# mpu_power.net
KiCad netlist of a schematic drawn in Altium Designer
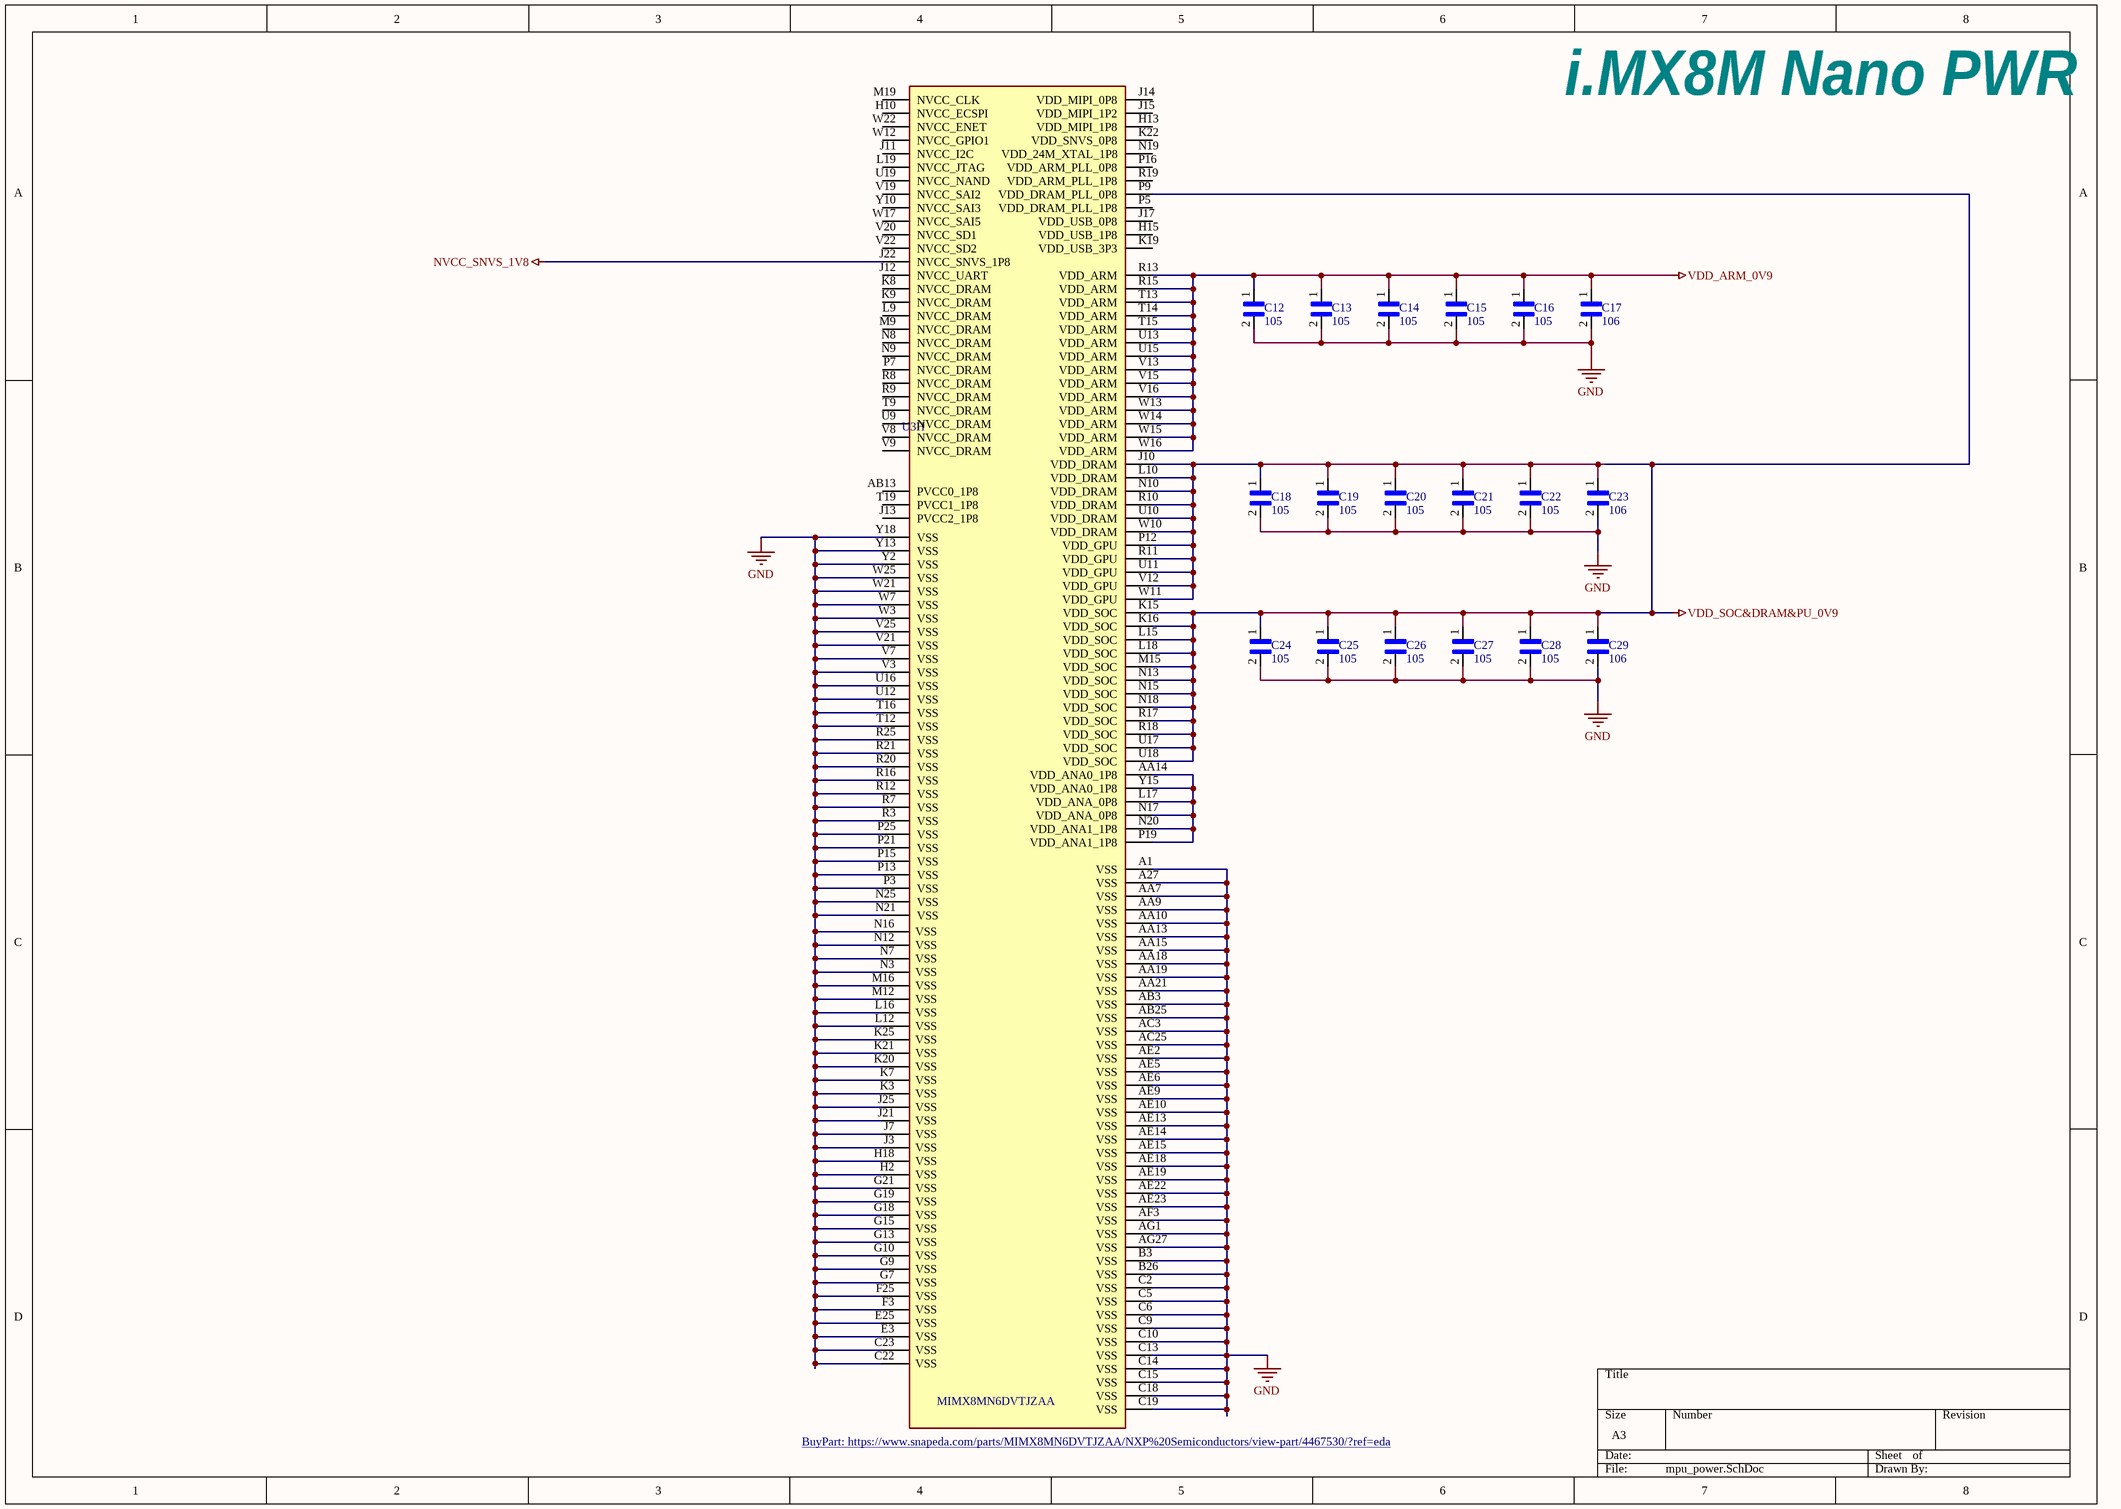
[diagram p0: mpu_power.SchDoc]

(export (version "E")
  (design (tool "Eeschema 10.0.6"))
  (components
    (comp (ref "C12")
      (value "105")
      (footprint "RC0402")
      (description "Multilayer Ceramic Capacitor, 1 uF, 100 V, ï¿½ 10%, X7R, 0402 [1005 Metric]")
      (fields
        (field (name "MANUFACTURER") "Yageo")
        (field (name "MANUFACTURER PART NUMBER") "CC0402KRX5R5BB105")
      )
      (libsource (lib "imx8mnano") (part "CC0402KRX5R5BB105"))
    )
    (comp (ref "C13")
      (value "105")
      (footprint "RC0402")
      (description "Multilayer Ceramic Capacitor, 1 uF, 100 V, ï¿½ 10%, X7R, 0402 [1005 Metric]")
      (fields
        (field (name "MANUFACTURER") "Yageo")
        (field (name "MANUFACTURER PART NUMBER") "CC0402KRX5R5BB105")
      )
      (libsource (lib "imx8mnano") (part "CC0402KRX5R5BB105"))
    )
    (comp (ref "C14")
      (value "105")
      (footprint "RC0402")
      (description "Multilayer Ceramic Capacitor, 1 uF, 100 V, ï¿½ 10%, X7R, 0402 [1005 Metric]")
      (fields
        (field (name "MANUFACTURER") "Yageo")
        (field (name "MANUFACTURER PART NUMBER") "CC0402KRX5R5BB105")
      )
      (libsource (lib "imx8mnano") (part "CC0402KRX5R5BB105"))
    )
    (comp (ref "C15")
      (value "105")
      (footprint "RC0402")
      (description "Multilayer Ceramic Capacitor, 1 uF, 100 V, ï¿½ 10%, X7R, 0402 [1005 Metric]")
      (fields
        (field (name "MANUFACTURER") "Yageo")
        (field (name "MANUFACTURER PART NUMBER") "CC0402KRX5R5BB105")
      )
      (libsource (lib "imx8mnano") (part "CC0402KRX5R5BB105"))
    )
    (comp (ref "C16")
      (value "105")
      (footprint "RC0402")
      (description "Multilayer Ceramic Capacitor, 1 uF, 100 V, ï¿½ 10%, X7R, 0402 [1005 Metric]")
      (fields
        (field (name "MANUFACTURER") "Yageo")
        (field (name "MANUFACTURER PART NUMBER") "CC0402KRX5R5BB105")
      )
      (libsource (lib "imx8mnano") (part "CC0402KRX5R5BB105"))
    )
    (comp (ref "C17")
      (value "106")
      (footprint "CL05A106MQ5NUNC")
      (description "Multilayer Ceramic Capacitor, 10 uF, 6.3 V, ï¿½ 20%, X5R, 0402 [1005 Metric]")
      (fields
        (field (name "MANUFACTURER") "Samsung")
        (field (name "MANUFACTURER PART NUMBER") "CL05A106MQ5NUNC")
      )
      (libsource (lib "imx8mnano") (part "CL05A106MQ5NUNC"))
    )
    (comp (ref "C18")
      (value "105")
      (footprint "RC0402")
      (description "Multilayer Ceramic Capacitor, 1 uF, 100 V, ï¿½ 10%, X7R, 0402 [1005 Metric]")
      (fields
        (field (name "MANUFACTURER") "Yageo")
        (field (name "MANUFACTURER PART NUMBER") "CC0402KRX5R5BB105")
      )
      (libsource (lib "imx8mnano") (part "CC0402KRX5R5BB105"))
    )
    (comp (ref "C19")
      (value "105")
      (footprint "RC0402")
      (description "Multilayer Ceramic Capacitor, 1 uF, 100 V, ï¿½ 10%, X7R, 0402 [1005 Metric]")
      (fields
        (field (name "MANUFACTURER") "Yageo")
        (field (name "MANUFACTURER PART NUMBER") "CC0402KRX5R5BB105")
      )
      (libsource (lib "imx8mnano") (part "CC0402KRX5R5BB105"))
    )
    (comp (ref "C20")
      (value "105")
      (footprint "RC0402")
      (description "Multilayer Ceramic Capacitor, 1 uF, 100 V, ï¿½ 10%, X7R, 0402 [1005 Metric]")
      (fields
        (field (name "MANUFACTURER") "Yageo")
        (field (name "MANUFACTURER PART NUMBER") "CC0402KRX5R5BB105")
      )
      (libsource (lib "imx8mnano") (part "CC0402KRX5R5BB105"))
    )
    (comp (ref "C21")
      (value "105")
      (footprint "RC0402")
      (description "Multilayer Ceramic Capacitor, 1 uF, 100 V, ï¿½ 10%, X7R, 0402 [1005 Metric]")
      (fields
        (field (name "MANUFACTURER") "Yageo")
        (field (name "MANUFACTURER PART NUMBER") "CC0402KRX5R5BB105")
      )
      (libsource (lib "imx8mnano") (part "CC0402KRX5R5BB105"))
    )
    (comp (ref "C22")
      (value "105")
      (footprint "RC0402")
      (description "Multilayer Ceramic Capacitor, 1 uF, 100 V, ï¿½ 10%, X7R, 0402 [1005 Metric]")
      (fields
        (field (name "MANUFACTURER") "Yageo")
        (field (name "MANUFACTURER PART NUMBER") "CC0402KRX5R5BB105")
      )
      (libsource (lib "imx8mnano") (part "CC0402KRX5R5BB105"))
    )
    (comp (ref "C23")
      (value "106")
      (footprint "CL05A106MQ5NUNC")
      (description "Multilayer Ceramic Capacitor, 10 uF, 6.3 V, ï¿½ 20%, X5R, 0402 [1005 Metric]")
      (fields
        (field (name "MANUFACTURER") "Samsung")
        (field (name "MANUFACTURER PART NUMBER") "CL05A106MQ5NUNC")
      )
      (libsource (lib "imx8mnano") (part "CL05A106MQ5NUNC"))
    )
    (comp (ref "C24")
      (value "105")
      (footprint "RC0402")
      (description "Multilayer Ceramic Capacitor, 1 uF, 100 V, ï¿½ 10%, X7R, 0402 [1005 Metric]")
      (fields
        (field (name "MANUFACTURER") "Yageo")
        (field (name "MANUFACTURER PART NUMBER") "CC0402KRX5R5BB105")
      )
      (libsource (lib "imx8mnano") (part "CC0402KRX5R5BB105"))
    )
    (comp (ref "C25")
      (value "105")
      (footprint "RC0402")
      (description "Multilayer Ceramic Capacitor, 1 uF, 100 V, ï¿½ 10%, X7R, 0402 [1005 Metric]")
      (fields
        (field (name "MANUFACTURER") "Yageo")
        (field (name "MANUFACTURER PART NUMBER") "CC0402KRX5R5BB105")
      )
      (libsource (lib "imx8mnano") (part "CC0402KRX5R5BB105"))
    )
    (comp (ref "C26")
      (value "105")
      (footprint "RC0402")
      (description "Multilayer Ceramic Capacitor, 1 uF, 100 V, ï¿½ 10%, X7R, 0402 [1005 Metric]")
      (fields
        (field (name "MANUFACTURER") "Yageo")
        (field (name "MANUFACTURER PART NUMBER") "CC0402KRX5R5BB105")
      )
      (libsource (lib "imx8mnano") (part "CC0402KRX5R5BB105"))
    )
    (comp (ref "C27")
      (value "105")
      (footprint "RC0402")
      (description "Multilayer Ceramic Capacitor, 1 uF, 100 V, ï¿½ 10%, X7R, 0402 [1005 Metric]")
      (fields
        (field (name "MANUFACTURER") "Yageo")
        (field (name "MANUFACTURER PART NUMBER") "CC0402KRX5R5BB105")
      )
      (libsource (lib "imx8mnano") (part "CC0402KRX5R5BB105"))
    )
    (comp (ref "C28")
      (value "105")
      (footprint "RC0402")
      (description "Multilayer Ceramic Capacitor, 1 uF, 100 V, ï¿½ 10%, X7R, 0402 [1005 Metric]")
      (fields
        (field (name "MANUFACTURER") "Yageo")
        (field (name "MANUFACTURER PART NUMBER") "CC0402KRX5R5BB105")
      )
      (libsource (lib "imx8mnano") (part "CC0402KRX5R5BB105"))
    )
    (comp (ref "C29")
      (value "106")
      (footprint "CL05A106MQ5NUNC")
      (description "Multilayer Ceramic Capacitor, 10 uF, 6.3 V, ï¿½ 20%, X5R, 0402 [1005 Metric]")
      (fields
        (field (name "MANUFACTURER") "Samsung")
        (field (name "MANUFACTURER PART NUMBER") "CL05A106MQ5NUNC")
      )
      (libsource (lib "imx8mnano") (part "CL05A106MQ5NUNC"))
    )
    (comp (ref "U3")
      (value "MIMX8MN6DVTJZAA")
      (footprint "BGA486N50P27X27_1400X1400X125N")
      (description "ARMÂ® CortexÂ®-A53 Microprocessor IC i.MX8MN 4 Core, 32-Bit 1.5GHz 486-LFBGA (14x14)")
      (fields
        (field (name "MF") "NXP USA Inc.")
        (field (name "BUYPART") "https://www.snapeda.com/parts/MIMX8MN6DVTJZAA/NXP%20Semiconductors/view-part/4467530/?ref=eda")
      )
      (libsource (lib "imx8mnano") (part "MIMX8MN6DVTJZAA"))
    )
  )
  (nets
    (net (code "1") (name "GND") (class "Default")
      (node (ref "C12") (pin "2") (pinfunction "2_2") (pintype "passive"))
      (node (ref "C13") (pin "2") (pinfunction "2_2") (pintype "passive"))
      (node (ref "C14") (pin "2") (pinfunction "2_2") (pintype "passive"))
      (node (ref "C15") (pin "2") (pinfunction "2_2") (pintype "passive"))
      (node (ref "C16") (pin "2") (pinfunction "2_2") (pintype "passive"))
      (node (ref "C17") (pin "2") (pinfunction "2_2") (pintype "passive"))
      (node (ref "C18") (pin "2") (pinfunction "2_2") (pintype "passive"))
      (node (ref "C19") (pin "2") (pinfunction "2_2") (pintype "passive"))
      (node (ref "C20") (pin "2") (pinfunction "2_2") (pintype "passive"))
      (node (ref "C21") (pin "2") (pinfunction "2_2") (pintype "passive"))
      (node (ref "C22") (pin "2") (pinfunction "2_2") (pintype "passive"))
      (node (ref "C23") (pin "2") (pinfunction "2_2") (pintype "passive"))
      (node (ref "C24") (pin "2") (pinfunction "2_2") (pintype "passive"))
      (node (ref "C25") (pin "2") (pinfunction "2_2") (pintype "passive"))
      (node (ref "C26") (pin "2") (pinfunction "2_2") (pintype "passive"))
      (node (ref "C27") (pin "2") (pinfunction "2_2") (pintype "passive"))
      (node (ref "C28") (pin "2") (pinfunction "2_2") (pintype "passive"))
      (node (ref "C29") (pin "2") (pinfunction "2_2") (pintype "passive"))
      (node (ref "U3") (pin "A1") (pinfunction "VSS_A1") (pintype "power_in"))
      (node (ref "U3") (pin "A27") (pinfunction "VSS_A27") (pintype "power_in"))
      (node (ref "U3") (pin "AA10") (pinfunction "VSS_AA10") (pintype "power_in"))
      (node (ref "U3") (pin "AA13") (pinfunction "VSS_AA13") (pintype "power_in"))
      (node (ref "U3") (pin "AA18") (pinfunction "VSS_AA18") (pintype "power_in"))
      (node (ref "U3") (pin "AA19") (pinfunction "VSS_AA19") (pintype "power_in"))
      (node (ref "U3") (pin "AA21") (pinfunction "VSS_AA21") (pintype "power_in"))
      (node (ref "U3") (pin "AA7") (pinfunction "VSS_AA7") (pintype "power_in"))
      (node (ref "U3") (pin "AA9") (pinfunction "VSS_AA9") (pintype "power_in"))
      (node (ref "U3") (pin "AB25") (pinfunction "VSS_AB25") (pintype "power_in"))
      (node (ref "U3") (pin "AB3") (pinfunction "VSS_AB3") (pintype "power_in"))
      (node (ref "U3") (pin "AC25") (pinfunction "VSS_AC25") (pintype "power_in"))
      (node (ref "U3") (pin "AC3") (pinfunction "VSS_AC3") (pintype "power_in"))
      (node (ref "U3") (pin "AE10") (pinfunction "VSS_AE10") (pintype "power_in"))
      (node (ref "U3") (pin "AE13") (pinfunction "VSS_AE13") (pintype "power_in"))
      (node (ref "U3") (pin "AE14") (pinfunction "VSS_AE14") (pintype "power_in"))
      (node (ref "U3") (pin "AE15") (pinfunction "VSS_AE15") (pintype "power_in"))
      (node (ref "U3") (pin "AE18") (pinfunction "VSS_AE18") (pintype "power_in"))
      (node (ref "U3") (pin "AE19") (pinfunction "VSS_AE19") (pintype "power_in"))
      (node (ref "U3") (pin "AE2") (pinfunction "VSS_AE2") (pintype "power_in"))
      (node (ref "U3") (pin "AE22") (pinfunction "VSS_AE22") (pintype "power_in"))
      (node (ref "U3") (pin "AE23") (pinfunction "VSS_AE23") (pintype "power_in"))
      (node (ref "U3") (pin "AE5") (pinfunction "VSS_AE5") (pintype "power_in"))
      (node (ref "U3") (pin "AE6") (pinfunction "VSS_AE6") (pintype "power_in"))
      (node (ref "U3") (pin "AE9") (pinfunction "VSS_AE9") (pintype "power_in"))
      (node (ref "U3") (pin "AF3") (pinfunction "VSS_AF3") (pintype "power_in"))
      (node (ref "U3") (pin "AG1") (pinfunction "VSS_AG1") (pintype "power_in"))
      (node (ref "U3") (pin "AG27") (pinfunction "VSS_AG27") (pintype "power_in"))
      (node (ref "U3") (pin "B26") (pinfunction "VSS_B26") (pintype "power_in"))
      (node (ref "U3") (pin "B3") (pinfunction "VSS_B3") (pintype "power_in"))
      (node (ref "U3") (pin "C10") (pinfunction "VSS_C10") (pintype "power_in"))
      (node (ref "U3") (pin "C13") (pinfunction "VSS_C13") (pintype "power_in"))
      (node (ref "U3") (pin "C14") (pinfunction "VSS_C14") (pintype "power_in"))
      (node (ref "U3") (pin "C15") (pinfunction "VSS_C15") (pintype "power_in"))
      (node (ref "U3") (pin "C18") (pinfunction "VSS_C18") (pintype "power_in"))
      (node (ref "U3") (pin "C19") (pinfunction "VSS_C19") (pintype "power_in"))
      (node (ref "U3") (pin "C2") (pinfunction "VSS_C2") (pintype "power_in"))
      (node (ref "U3") (pin "C22") (pinfunction "VSS_C22") (pintype "power_in"))
      (node (ref "U3") (pin "C23") (pinfunction "VSS_C23") (pintype "power_in"))
      (node (ref "U3") (pin "C5") (pinfunction "VSS_C5") (pintype "power_in"))
      (node (ref "U3") (pin "C6") (pinfunction "VSS_C6") (pintype "power_in"))
      (node (ref "U3") (pin "C9") (pinfunction "VSS_C9") (pintype "power_in"))
      (node (ref "U3") (pin "E25") (pinfunction "VSS_E25") (pintype "power_in"))
      (node (ref "U3") (pin "E3") (pinfunction "VSS_E3") (pintype "power_in"))
      (node (ref "U3") (pin "F25") (pinfunction "VSS_F25") (pintype "power_in"))
      (node (ref "U3") (pin "F3") (pinfunction "VSS_F3") (pintype "power_in"))
      (node (ref "U3") (pin "G10") (pinfunction "VSS_G10") (pintype "power_in"))
      (node (ref "U3") (pin "G13") (pinfunction "VSS_G13") (pintype "power_in"))
      (node (ref "U3") (pin "G15") (pinfunction "VSS_G15") (pintype "power_in"))
      (node (ref "U3") (pin "G18") (pinfunction "VSS_G18") (pintype "power_in"))
      (node (ref "U3") (pin "G19") (pinfunction "VSS_G19") (pintype "power_in"))
      (node (ref "U3") (pin "G21") (pinfunction "VSS_G21") (pintype "power_in"))
      (node (ref "U3") (pin "G7") (pinfunction "VSS_G7") (pintype "power_in"))
      (node (ref "U3") (pin "G9") (pinfunction "VSS_G9") (pintype "power_in"))
      (node (ref "U3") (pin "H18") (pinfunction "VSS_H18") (pintype "power_in"))
      (node (ref "U3") (pin "H2") (pinfunction "VSS_H2") (pintype "power_in"))
      (node (ref "U3") (pin "J21") (pinfunction "VSS_J21") (pintype "power_in"))
      (node (ref "U3") (pin "J25") (pinfunction "VSS_J25") (pintype "power_in"))
      (node (ref "U3") (pin "J3") (pinfunction "VSS_J3") (pintype "power_in"))
      (node (ref "U3") (pin "J7") (pinfunction "VSS_J7") (pintype "power_in"))
      (node (ref "U3") (pin "K20") (pinfunction "VSS_K20") (pintype "power_in"))
      (node (ref "U3") (pin "K21") (pinfunction "VSS_K21") (pintype "power_in"))
      (node (ref "U3") (pin "K25") (pinfunction "VSS_K25") (pintype "power_in"))
      (node (ref "U3") (pin "K3") (pinfunction "VSS_K3") (pintype "power_in"))
      (node (ref "U3") (pin "K7") (pinfunction "VSS_K7") (pintype "power_in"))
      (node (ref "U3") (pin "L12") (pinfunction "VSS_L12") (pintype "power_in"))
      (node (ref "U3") (pin "L16") (pinfunction "VSS_L16") (pintype "power_in"))
      (node (ref "U3") (pin "M12") (pinfunction "VSS_M12") (pintype "power_in"))
      (node (ref "U3") (pin "M16") (pinfunction "VSS_M16") (pintype "power_in"))
      (node (ref "U3") (pin "N12") (pinfunction "VSS_N12") (pintype "power_in"))
      (node (ref "U3") (pin "N16") (pinfunction "VSS_N16") (pintype "power_in"))
      (node (ref "U3") (pin "N21") (pinfunction "VSS_N21") (pintype "power_in"))
      (node (ref "U3") (pin "N25") (pinfunction "VSS_N25") (pintype "power_in"))
      (node (ref "U3") (pin "N3") (pinfunction "VSS_N3") (pintype "power_in"))
      (node (ref "U3") (pin "N7") (pinfunction "VSS_N7") (pintype "power_in"))
      (node (ref "U3") (pin "P13") (pinfunction "VSS_P13") (pintype "power_in"))
      (node (ref "U3") (pin "P15") (pinfunction "VSS_P15") (pintype "power_in"))
      (node (ref "U3") (pin "P21") (pinfunction "VSS_P21") (pintype "power_in"))
      (node (ref "U3") (pin "P25") (pinfunction "VSS_P25") (pintype "power_in"))
      (node (ref "U3") (pin "P3") (pinfunction "VSS_P3") (pintype "power_in"))
      (node (ref "U3") (pin "R12") (pinfunction "VSS_R12") (pintype "power_in"))
      (node (ref "U3") (pin "R16") (pinfunction "VSS_R16") (pintype "power_in"))
      (node (ref "U3") (pin "R20") (pinfunction "VSS_R20") (pintype "power_in"))
      (node (ref "U3") (pin "R21") (pinfunction "VSS_R21") (pintype "power_in"))
      (node (ref "U3") (pin "R25") (pinfunction "VSS_R25") (pintype "power_in"))
      (node (ref "U3") (pin "R3") (pinfunction "VSS_R3") (pintype "power_in"))
      (node (ref "U3") (pin "R7") (pinfunction "VSS_R7") (pintype "power_in"))
      (node (ref "U3") (pin "T12") (pinfunction "VSS_T12") (pintype "power_in"))
      (node (ref "U3") (pin "T16") (pinfunction "VSS_T16") (pintype "power_in"))
      (node (ref "U3") (pin "U12") (pinfunction "VSS_U12") (pintype "power_in"))
      (node (ref "U3") (pin "U16") (pinfunction "VSS_U16") (pintype "power_in"))
      (node (ref "U3") (pin "V21") (pinfunction "VSS_V21") (pintype "power_in"))
      (node (ref "U3") (pin "V25") (pinfunction "VSS_V25") (pintype "power_in"))
      (node (ref "U3") (pin "V3") (pinfunction "VSS_V3") (pintype "power_in"))
      (node (ref "U3") (pin "V7") (pinfunction "VSS_V7") (pintype "power_in"))
      (node (ref "U3") (pin "W21") (pinfunction "VSS_W21") (pintype "power_in"))
      (node (ref "U3") (pin "W25") (pinfunction "VSS_W25") (pintype "power_in"))
      (node (ref "U3") (pin "W3") (pinfunction "VSS_W3") (pintype "power_in"))
      (node (ref "U3") (pin "W7") (pinfunction "VSS_W7") (pintype "power_in"))
      (node (ref "U3") (pin "Y13") (pinfunction "VSS_Y13") (pintype "power_in"))
      (node (ref "U3") (pin "Y18") (pinfunction "VSS_Y18") (pintype "power_in"))
      (node (ref "U3") (pin "Y2") (pinfunction "VSS_Y2") (pintype "power_in"))
    )
    (net (code "2") (name "NVCC_SNVS_1V8") (class "Default")
      (node (ref "U3") (pin "J22") (pinfunction "NVCC_SNVS_1P8_J22") (pintype "power_in"))
    )
    (net (code "3") (name "Net-(U3H-VDD_ANA0_1P8-PadAA14)") (class "Default")
      (node (ref "U3") (pin "AA14") (pinfunction "VDD_ANA0_1P8_AA14") (pintype "power_in"))
      (node (ref "U3") (pin "L17") (pinfunction "VDD_ANA_0P8_L17") (pintype "power_in"))
      (node (ref "U3") (pin "N17") (pinfunction "VDD_ANA_0P8_N17") (pintype "power_in"))
      (node (ref "U3") (pin "N20") (pinfunction "VDD_ANA1_1P8_N20") (pintype "power_in"))
      (node (ref "U3") (pin "P19") (pinfunction "VDD_ANA1_1P8_P19") (pintype "power_in"))
      (node (ref "U3") (pin "Y15") (pinfunction "VDD_ANA0_1P8_Y15") (pintype "power_in"))
    )
    (net (code "4") (name "VDD_ARM_0V9") (class "Default")
      (node (ref "C12") (pin "1") (pinfunction "1_1") (pintype "passive"))
      (node (ref "C13") (pin "1") (pinfunction "1_1") (pintype "passive"))
      (node (ref "C14") (pin "1") (pinfunction "1_1") (pintype "passive"))
      (node (ref "C15") (pin "1") (pinfunction "1_1") (pintype "passive"))
      (node (ref "C16") (pin "1") (pinfunction "1_1") (pintype "passive"))
      (node (ref "C17") (pin "1") (pinfunction "1_1") (pintype "passive"))
      (node (ref "U3") (pin "R13") (pinfunction "VDD_ARM_R13") (pintype "power_in"))
      (node (ref "U3") (pin "R15") (pinfunction "VDD_ARM_R15") (pintype "power_in"))
      (node (ref "U3") (pin "T13") (pinfunction "VDD_ARM_T13") (pintype "power_in"))
      (node (ref "U3") (pin "T14") (pinfunction "VDD_ARM_T14") (pintype "power_in"))
      (node (ref "U3") (pin "T15") (pinfunction "VDD_ARM_T15") (pintype "power_in"))
      (node (ref "U3") (pin "U13") (pinfunction "VDD_ARM_U13") (pintype "power_in"))
      (node (ref "U3") (pin "U15") (pinfunction "VDD_ARM_U15") (pintype "power_in"))
      (node (ref "U3") (pin "V13") (pinfunction "VDD_ARM_V13") (pintype "power_in"))
      (node (ref "U3") (pin "V15") (pinfunction "VDD_ARM_V15") (pintype "power_in"))
      (node (ref "U3") (pin "V16") (pinfunction "VDD_ARM_V16") (pintype "power_in"))
      (node (ref "U3") (pin "W13") (pinfunction "VDD_ARM_W13") (pintype "power_in"))
      (node (ref "U3") (pin "W14") (pinfunction "VDD_ARM_W14") (pintype "power_in"))
      (node (ref "U3") (pin "W15") (pinfunction "VDD_ARM_W15") (pintype "power_in"))
      (node (ref "U3") (pin "W16") (pinfunction "VDD_ARM_W16") (pintype "power_in"))
    )
    (net (code "5") (name "VDD_SOC&DRAM&PU_0V9") (class "Default")
      (node (ref "C18") (pin "1") (pinfunction "1_1") (pintype "passive"))
      (node (ref "C19") (pin "1") (pinfunction "1_1") (pintype "passive"))
      (node (ref "C20") (pin "1") (pinfunction "1_1") (pintype "passive"))
      (node (ref "C21") (pin "1") (pinfunction "1_1") (pintype "passive"))
      (node (ref "C22") (pin "1") (pinfunction "1_1") (pintype "passive"))
      (node (ref "C23") (pin "1") (pinfunction "1_1") (pintype "passive"))
      (node (ref "C24") (pin "1") (pinfunction "1_1") (pintype "passive"))
      (node (ref "C25") (pin "1") (pinfunction "1_1") (pintype "passive"))
      (node (ref "C26") (pin "1") (pinfunction "1_1") (pintype "passive"))
      (node (ref "C27") (pin "1") (pinfunction "1_1") (pintype "passive"))
      (node (ref "C28") (pin "1") (pinfunction "1_1") (pintype "passive"))
      (node (ref "C29") (pin "1") (pinfunction "1_1") (pintype "passive"))
      (node (ref "U3") (pin "J10") (pinfunction "VDD_DRAM_J10") (pintype "power_in"))
      (node (ref "U3") (pin "K15") (pinfunction "VDD_SOC_K15") (pintype "power_in"))
      (node (ref "U3") (pin "K16") (pinfunction "VDD_SOC_K16") (pintype "power_in"))
      (node (ref "U3") (pin "L10") (pinfunction "VDD_DRAM_L10") (pintype "power_in"))
      (node (ref "U3") (pin "L15") (pinfunction "VDD_SOC_L15") (pintype "power_in"))
      (node (ref "U3") (pin "L18") (pinfunction "VDD_SOC_L18") (pintype "power_in"))
      (node (ref "U3") (pin "M15") (pinfunction "VDD_SOC_M15") (pintype "power_in"))
      (node (ref "U3") (pin "N10") (pinfunction "VDD_DRAM_N10") (pintype "power_in"))
      (node (ref "U3") (pin "N13") (pinfunction "VDD_SOC_N13") (pintype "power_in"))
      (node (ref "U3") (pin "N15") (pinfunction "VDD_SOC_N15") (pintype "power_in"))
      (node (ref "U3") (pin "N18") (pinfunction "VDD_SOC_N18") (pintype "power_in"))
      (node (ref "U3") (pin "P12") (pinfunction "VDD_GPU_P12") (pintype "power_in"))
      (node (ref "U3") (pin "P9") (pinfunction "VDD_DRAM_PLL_0P8_P9") (pintype "power_in"))
      (node (ref "U3") (pin "R10") (pinfunction "VDD_DRAM_R10") (pintype "power_in"))
      (node (ref "U3") (pin "R11") (pinfunction "VDD_GPU_R11") (pintype "power_in"))
      (node (ref "U3") (pin "R17") (pinfunction "VDD_SOC_R17") (pintype "power_in"))
      (node (ref "U3") (pin "R18") (pinfunction "VDD_SOC_R18") (pintype "power_in"))
      (node (ref "U3") (pin "U10") (pinfunction "VDD_DRAM_U10") (pintype "power_in"))
      (node (ref "U3") (pin "U11") (pinfunction "VDD_GPU_U11") (pintype "power_in"))
      (node (ref "U3") (pin "U17") (pinfunction "VDD_SOC_U17") (pintype "power_in"))
      (node (ref "U3") (pin "U18") (pinfunction "VDD_SOC_U18") (pintype "power_in"))
      (node (ref "U3") (pin "V12") (pinfunction "VDD_GPU_V12") (pintype "power_in"))
      (node (ref "U3") (pin "W10") (pinfunction "VDD_DRAM_W10") (pintype "power_in"))
      (node (ref "U3") (pin "W11") (pinfunction "VDD_GPU_W11") (pintype "power_in"))
    )
    (net (code "6") (name "unconnected-(U3H-NVCC_CLK-PadM19)") (class "Default")
      (node (ref "U3") (pin "M19") (pinfunction "NVCC_CLK_M19") (pintype "power_in"))
    )
    (net (code "7") (name "unconnected-(U3H-NVCC_DRAM-PadK8)") (class "Default")
      (node (ref "U3") (pin "K8") (pinfunction "NVCC_DRAM_K8") (pintype "power_in"))
    )
    (net (code "8") (name "unconnected-(U3H-NVCC_DRAM-PadK9)") (class "Default")
      (node (ref "U3") (pin "K9") (pinfunction "NVCC_DRAM_K9") (pintype "power_in"))
    )
    (net (code "9") (name "unconnected-(U3H-NVCC_DRAM-PadL9)") (class "Default")
      (node (ref "U3") (pin "L9") (pinfunction "NVCC_DRAM_L9") (pintype "power_in"))
    )
    (net (code "10") (name "unconnected-(U3H-NVCC_DRAM-PadM9)") (class "Default")
      (node (ref "U3") (pin "M9") (pinfunction "NVCC_DRAM_M9") (pintype "power_in"))
    )
    (net (code "11") (name "unconnected-(U3H-NVCC_DRAM-PadN8)") (class "Default")
      (node (ref "U3") (pin "N8") (pinfunction "NVCC_DRAM_N8") (pintype "power_in"))
    )
    (net (code "12") (name "unconnected-(U3H-NVCC_DRAM-PadN9)") (class "Default")
      (node (ref "U3") (pin "N9") (pinfunction "NVCC_DRAM_N9") (pintype "power_in"))
    )
    (net (code "13") (name "unconnected-(U3H-NVCC_DRAM-PadP7)") (class "Default")
      (node (ref "U3") (pin "P7") (pinfunction "NVCC_DRAM_P7") (pintype "power_in"))
    )
    (net (code "14") (name "unconnected-(U3H-NVCC_DRAM-PadR8)") (class "Default")
      (node (ref "U3") (pin "R8") (pinfunction "NVCC_DRAM_R8") (pintype "power_in"))
    )
    (net (code "15") (name "unconnected-(U3H-NVCC_DRAM-PadR9)") (class "Default")
      (node (ref "U3") (pin "R9") (pinfunction "NVCC_DRAM_R9") (pintype "power_in"))
    )
    (net (code "16") (name "unconnected-(U3H-NVCC_DRAM-PadT9)") (class "Default")
      (node (ref "U3") (pin "T9") (pinfunction "NVCC_DRAM_T9") (pintype "power_in"))
    )
    (net (code "17") (name "unconnected-(U3H-NVCC_DRAM-PadU9)") (class "Default")
      (node (ref "U3") (pin "U9") (pinfunction "NVCC_DRAM_U9") (pintype "power_in"))
    )
    (net (code "18") (name "unconnected-(U3H-NVCC_DRAM-PadV8)") (class "Default")
      (node (ref "U3") (pin "V8") (pinfunction "NVCC_DRAM_V8") (pintype "power_in"))
    )
    (net (code "19") (name "unconnected-(U3H-NVCC_DRAM-PadV9)") (class "Default")
      (node (ref "U3") (pin "V9") (pinfunction "NVCC_DRAM_V9") (pintype "power_in"))
    )
    (net (code "20") (name "unconnected-(U3H-NVCC_ECSPI-PadH10)") (class "Default")
      (node (ref "U3") (pin "H10") (pinfunction "NVCC_ECSPI_H10") (pintype "power_in"))
    )
    (net (code "21") (name "unconnected-(U3H-NVCC_ENET-PadW22)") (class "Default")
      (node (ref "U3") (pin "W22") (pinfunction "NVCC_ENET_W22") (pintype "power_in"))
    )
    (net (code "22") (name "unconnected-(U3H-NVCC_GPIO1-PadW12)") (class "Default")
      (node (ref "U3") (pin "W12") (pinfunction "NVCC_GPIO1_W12") (pintype "power_in"))
    )
    (net (code "23") (name "unconnected-(U3H-NVCC_I2C-PadJ11)") (class "Default")
      (node (ref "U3") (pin "J11") (pinfunction "NVCC_I2C_J11") (pintype "power_in"))
    )
    (net (code "24") (name "unconnected-(U3H-NVCC_JTAG-PadL19)") (class "Default")
      (node (ref "U3") (pin "L19") (pinfunction "NVCC_JTAG_L19") (pintype "power_in"))
    )
    (net (code "25") (name "unconnected-(U3H-NVCC_NAND-PadU19)") (class "Default")
      (node (ref "U3") (pin "U19") (pinfunction "NVCC_NAND_U19") (pintype "power_in"))
    )
    (net (code "26") (name "unconnected-(U3H-NVCC_SAI2-PadV19)") (class "Default")
      (node (ref "U3") (pin "V19") (pinfunction "NVCC_SAI2_V19") (pintype "power_in"))
    )
    (net (code "27") (name "unconnected-(U3H-NVCC_SAI3-PadY10)") (class "Default")
      (node (ref "U3") (pin "Y10") (pinfunction "NVCC_SAI3_Y10") (pintype "power_in"))
    )
    (net (code "28") (name "unconnected-(U3H-NVCC_SAI5-PadW17)") (class "Default")
      (node (ref "U3") (pin "W17") (pinfunction "NVCC_SAI5_W17") (pintype "power_in"))
    )
    (net (code "29") (name "unconnected-(U3H-NVCC_SD1-PadV20)") (class "Default")
      (node (ref "U3") (pin "V20") (pinfunction "NVCC_SD1_V20") (pintype "power_in"))
    )
    (net (code "30") (name "unconnected-(U3H-NVCC_SD2-PadV22)") (class "Default")
      (node (ref "U3") (pin "V22") (pinfunction "NVCC_SD2_V22") (pintype "power_in"))
    )
    (net (code "31") (name "unconnected-(U3H-NVCC_UART-PadJ12)") (class "Default")
      (node (ref "U3") (pin "J12") (pinfunction "NVCC_UART_J12") (pintype "power_in"))
    )
    (net (code "32") (name "unconnected-(U3H-PVCC0_1P8-PadAB13)") (class "Default")
      (node (ref "U3") (pin "AB13") (pinfunction "PVCC0_1P8_AB13") (pintype "power_in"))
    )
    (net (code "33") (name "unconnected-(U3H-PVCC1_1P8-PadT19)") (class "Default")
      (node (ref "U3") (pin "T19") (pinfunction "PVCC1_1P8_T19") (pintype "power_in"))
    )
    (net (code "34") (name "unconnected-(U3H-PVCC2_1P8-PadJ13)") (class "Default")
      (node (ref "U3") (pin "J13") (pinfunction "PVCC2_1P8_J13") (pintype "power_in"))
    )
    (net (code "35") (name "unconnected-(U3H-VDD_24M_XTAL_1P8-PadN19)") (class "Default")
      (node (ref "U3") (pin "N19") (pinfunction "VDD_24M_XTAL_1P8_N19") (pintype "power_in"))
    )
    (net (code "36") (name "unconnected-(U3H-VDD_ARM_PLL_0P8-PadP16)") (class "Default")
      (node (ref "U3") (pin "P16") (pinfunction "VDD_ARM_PLL_0P8_P16") (pintype "power_in"))
    )
    (net (code "37") (name "unconnected-(U3H-VDD_ARM_PLL_1P8-PadR19)") (class "Default")
      (node (ref "U3") (pin "R19") (pinfunction "VDD_ARM_PLL_1P8_R19") (pintype "power_in"))
    )
    (net (code "38") (name "unconnected-(U3H-VDD_DRAM_PLL_1P8-PadP5)") (class "Default")
      (node (ref "U3") (pin "P5") (pinfunction "VDD_DRAM_PLL_1P8_P5") (pintype "power_in"))
    )
    (net (code "39") (name "unconnected-(U3H-VDD_MIPI_0P8-PadJ14)") (class "Default")
      (node (ref "U3") (pin "J14") (pinfunction "VDD_MIPI_0P8_J14") (pintype "power_in"))
    )
    (net (code "40") (name "unconnected-(U3H-VDD_MIPI_1P2-PadJ15)") (class "Default")
      (node (ref "U3") (pin "J15") (pinfunction "VDD_MIPI_1P2_J15") (pintype "power_in"))
    )
    (net (code "41") (name "unconnected-(U3H-VDD_MIPI_1P8-PadH13)") (class "Default")
      (node (ref "U3") (pin "H13") (pinfunction "VDD_MIPI_1P8_H13") (pintype "power_in"))
    )
    (net (code "42") (name "unconnected-(U3H-VDD_SNVS_0P8-PadK22)") (class "Default")
      (node (ref "U3") (pin "K22") (pinfunction "VDD_SNVS_0P8_K22") (pintype "power_in"))
    )
    (net (code "43") (name "unconnected-(U3H-VDD_USB_0P8-PadJ17)") (class "Default")
      (node (ref "U3") (pin "J17") (pinfunction "VDD_USB_0P8_J17") (pintype "power_in"))
    )
    (net (code "44") (name "unconnected-(U3H-VDD_USB_1P8-PadH15)") (class "Default")
      (node (ref "U3") (pin "H15") (pinfunction "VDD_USB_1P8_H15") (pintype "power_in"))
    )
    (net (code "45") (name "unconnected-(U3H-VDD_USB_3P3-PadK19)") (class "Default")
      (node (ref "U3") (pin "K19") (pinfunction "VDD_USB_3P3_K19") (pintype "power_in"))
    )
    (net (code "46") (name "unconnected-(U3H-VSS-PadAA15)") (class "Default")
      (node (ref "U3") (pin "AA15") (pinfunction "VSS_AA15") (pintype "power_in"))
    )
  )
)
